# Receiver.net
KiCad netlist of a schematic drawn in EAGLE
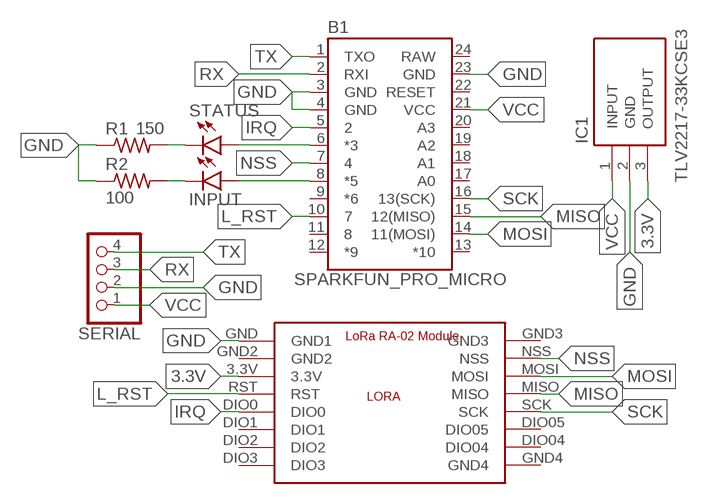
[diagram p0: schematic, sheet 1]

(export (version "E")
  (design (tool "Eeschema 10.0.6"))
  (components
    (comp (ref "B1")
      (value "SPARKFUN_PRO_MICRO")
      (footprint "eagle-import:SPARKFUN_PRO_MICRO")
      (libsource (lib "eagle-import") (part "SPARKFUN_PRO_MICRO"))
    )
    (comp (ref "IC1")
      (value "TLV2217-33KCSE3")
      (footprint "eagle-import:TO254P470X1016X1965-3P")
      (fields (field (name "MOUSER_PART_NUMBER") "595-TLV2217-33KCSE3"))
      (libsource (lib "eagle-import") (part "TLV2217-33KCSE3"))
    )
    (comp (ref "INPUT")
      (value "LEDSML0805")
      (footprint "eagle-import:SML0805")
      (libsource (lib "eagle-import") (part "LEDSML0805"))
    )
    (comp (ref "LORA")
      (value "LORA_RA-02_MODULE")
      (footprint "eagle-import:LORA_RA-02_MODULE_FOOTPRINT")
      (libsource (lib "eagle-import") (part "LORA_RA-02_MODULE"))
    )
    (comp (ref "R1")
      (value "150")
      (footprint "eagle-import:R0805")
      (libsource (lib "eagle-import") (part "R-US_R0805"))
    )
    (comp (ref "R2")
      (value "100")
      (footprint "eagle-import:R0805")
      (libsource (lib "eagle-import") (part "R-US_R0805"))
    )
    (comp (ref "SERIAL")
      (value "PINHD-1X4")
      (footprint "eagle-import:1X04")
      (libsource (lib "eagle-import") (part "PINHD-1X4"))
    )
    (comp (ref "STATUS")
      (value "LEDSML0805")
      (footprint "eagle-import:SML0805")
      (libsource (lib "eagle-import") (part "LEDSML0805"))
    )
  )
  (nets
    (net (code "1") (name "/RAW") (class "Default")
      (node (ref "B1") (pin "24") (pinfunction "RAW_24") (pintype "power_in"))
    )
    (net (code "2") (name "3.3V") (class "Default")
      (node (ref "IC1") (pin "3") (pinfunction "OUTPUT_3") (pintype "bidirectional"))
      (node (ref "LORA") (pin "3.3V") (pinfunction "3.3V_3.3V") (pintype "bidirectional"))
    )
    (net (code "3") (name "GND") (class "Default")
      (node (ref "B1") (pin "23") (pinfunction "GND_23") (pintype "power_in"))
      (node (ref "B1") (pin "3") (pinfunction "GND_3") (pintype "power_in"))
      (node (ref "B1") (pin "4") (pinfunction "GND_4") (pintype "power_in"))
      (node (ref "IC1") (pin "2") (pinfunction "GND_2") (pintype "bidirectional"))
      (node (ref "LORA") (pin "GND") (pinfunction "GND1_GND") (pintype "bidirectional"))
      (node (ref "R1") (pin "1") (pinfunction "1_1") (pintype "passive"))
      (node (ref "R2") (pin "1") (pinfunction "1_1") (pintype "passive"))
      (node (ref "SERIAL") (pin "2") (pinfunction "2_2") (pintype "passive"))
    )
    (net (code "4") (name "IRQ") (class "Default")
      (node (ref "B1") (pin "5") (pinfunction "2_5") (pintype "bidirectional"))
      (node (ref "LORA") (pin "DIO0") (pinfunction "DIO0_DIO0") (pintype "bidirectional"))
    )
    (net (code "5") (name "L_RST") (class "Default")
      (node (ref "B1") (pin "10") (pinfunction "7_10") (pintype "bidirectional"))
      (node (ref "LORA") (pin "RST") (pinfunction "RST_RST") (pintype "bidirectional"))
    )
    (net (code "6") (name "MISO") (class "Default")
      (node (ref "B1") (pin "15") (pinfunction "12(MISO)_15") (pintype "bidirectional"))
      (node (ref "LORA") (pin "MISO") (pinfunction "MISO_MISO") (pintype "bidirectional"))
    )
    (net (code "7") (name "MOSI") (class "Default")
      (node (ref "B1") (pin "14") (pinfunction "11(MOSI)_14") (pintype "bidirectional"))
      (node (ref "LORA") (pin "MOSI") (pinfunction "MOSI_MOSI") (pintype "bidirectional"))
    )
    (net (code "8") (name "NSS") (class "Default")
      (node (ref "B1") (pin "7") (pinfunction "4_7") (pintype "bidirectional"))
      (node (ref "LORA") (pin "NSS") (pinfunction "NSS_NSS") (pintype "bidirectional"))
    )
    (net (code "9") (name "Net-(B1-*3)") (class "Default")
      (node (ref "B1") (pin "6") (pinfunction "*3_6") (pintype "bidirectional"))
      (node (ref "STATUS") (pin "A") (pinfunction "A_A") (pintype "passive"))
    )
    (net (code "10") (name "Net-(B1-*5)") (class "Default")
      (node (ref "B1") (pin "8") (pinfunction "*5_8") (pintype "bidirectional"))
      (node (ref "INPUT") (pin "A") (pinfunction "A_A") (pintype "passive"))
    )
    (net (code "11") (name "Net-(INPUT-PadC)") (class "Default")
      (node (ref "INPUT") (pin "C") (pinfunction "C_C") (pintype "passive"))
      (node (ref "R2") (pin "2") (pinfunction "2_2") (pintype "passive"))
    )
    (net (code "12") (name "Net-(R1-Pad2)") (class "Default")
      (node (ref "R1") (pin "2") (pinfunction "2_2") (pintype "passive"))
      (node (ref "STATUS") (pin "C") (pinfunction "C_C") (pintype "passive"))
    )
    (net (code "13") (name "RX") (class "Default")
      (node (ref "B1") (pin "2") (pinfunction "RXI_2") (pintype "bidirectional"))
      (node (ref "SERIAL") (pin "3") (pinfunction "3_3") (pintype "passive"))
    )
    (net (code "14") (name "SCK") (class "Default")
      (node (ref "B1") (pin "16") (pinfunction "13(SCK)_16") (pintype "bidirectional"))
      (node (ref "LORA") (pin "SCK") (pinfunction "SCK_SCK") (pintype "bidirectional"))
    )
    (net (code "15") (name "TX") (class "Default")
      (node (ref "B1") (pin "1") (pinfunction "TXO_1") (pintype "bidirectional"))
      (node (ref "SERIAL") (pin "4") (pinfunction "4_4") (pintype "passive"))
    )
    (net (code "16") (name "VCC") (class "Default")
      (node (ref "B1") (pin "21") (pinfunction "VCC_21") (pintype "power_in"))
      (node (ref "IC1") (pin "1") (pinfunction "INPUT_1") (pintype "bidirectional"))
      (node (ref "SERIAL") (pin "1") (pinfunction "1_1") (pintype "passive"))
    )
    (net (code "17") (name "unconnected-(B1-*6-Pad9)") (class "Default")
      (node (ref "B1") (pin "9") (pinfunction "*6_9") (pintype "bidirectional"))
    )
    (net (code "18") (name "unconnected-(B1-*9-Pad12)") (class "Default")
      (node (ref "B1") (pin "12") (pinfunction "*9_12") (pintype "bidirectional"))
    )
    (net (code "19") (name "unconnected-(B1-*10-Pad13)") (class "Default")
      (node (ref "B1") (pin "13") (pinfunction "*10_13") (pintype "bidirectional"))
    )
    (net (code "20") (name "unconnected-(B1-8-Pad11)") (class "Default")
      (node (ref "B1") (pin "11") (pinfunction "8_11") (pintype "bidirectional"))
    )
    (net (code "21") (name "unconnected-(B1-A0-Pad17)") (class "Default")
      (node (ref "B1") (pin "17") (pinfunction "A0_17") (pintype "bidirectional"))
    )
    (net (code "22") (name "unconnected-(B1-A1-Pad18)") (class "Default")
      (node (ref "B1") (pin "18") (pinfunction "A1_18") (pintype "bidirectional"))
    )
    (net (code "23") (name "unconnected-(B1-A2-Pad19)") (class "Default")
      (node (ref "B1") (pin "19") (pinfunction "A2_19") (pintype "bidirectional"))
    )
    (net (code "24") (name "unconnected-(B1-A3-Pad20)") (class "Default")
      (node (ref "B1") (pin "20") (pinfunction "A3_20") (pintype "bidirectional"))
    )
    (net (code "25") (name "unconnected-(B1-RESET-Pad22)") (class "Default")
      (node (ref "B1") (pin "22") (pinfunction "RESET_22") (pintype "bidirectional"))
    )
    (net (code "26") (name "unconnected-(LORA-PadDIO1)") (class "Default")
      (node (ref "LORA") (pin "DIO1") (pinfunction "DIO1_DIO1") (pintype "bidirectional"))
    )
    (net (code "27") (name "unconnected-(LORA-PadDIO2)") (class "Default")
      (node (ref "LORA") (pin "DIO2") (pinfunction "DIO2_DIO2") (pintype "bidirectional"))
    )
    (net (code "28") (name "unconnected-(LORA-PadDIO3)") (class "Default")
      (node (ref "LORA") (pin "DIO3") (pinfunction "DIO3_DIO3") (pintype "bidirectional"))
    )
    (net (code "29") (name "unconnected-(LORA-PadDIO04)") (class "Default")
      (node (ref "LORA") (pin "DIO04") (pinfunction "DIO04_DIO04") (pintype "bidirectional"))
    )
    (net (code "30") (name "unconnected-(LORA-PadDIO05)") (class "Default")
      (node (ref "LORA") (pin "DIO05") (pinfunction "DIO05_DIO05") (pintype "bidirectional"))
    )
    (net (code "31") (name "unconnected-(LORA-PadGND2)") (class "Default")
      (node (ref "LORA") (pin "GND2") (pinfunction "GND2_GND2") (pintype "bidirectional"))
    )
    (net (code "32") (name "unconnected-(LORA-PadGND3)") (class "Default")
      (node (ref "LORA") (pin "GND3") (pinfunction "GND3_GND3") (pintype "bidirectional"))
    )
    (net (code "33") (name "unconnected-(LORA-PadGND4)") (class "Default")
      (node (ref "LORA") (pin "GND4") (pinfunction "GND4_GND4") (pintype "bidirectional"))
    )
  )
)
